# board.net
KiCad netlist of a schematic drawn in EAGLE
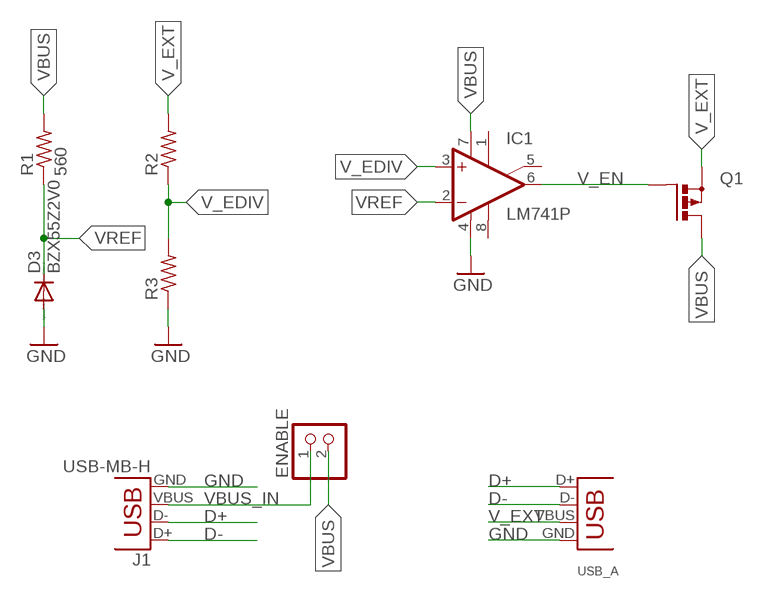
[diagram p0: schematic, sheet 1]

(export (version "E")
  (design (tool "Eeschema 10.0.6"))
  (components
    (comp (ref "D3")
      (value "BZX55Z2V0")
      (footprint "eagle-import:DO35-7")
      (libsource (lib "eagle-import") (part "1N4148DO35-7"))
    )
    (comp (ref "ENABLE")
      (value "PINHD-1X2")
      (footprint "eagle-import:1X02")
      (libsource (lib "eagle-import") (part "PINHD-1X2"))
    )
    (comp (ref "IC1")
      (value "LM741P")
      (footprint "eagle-import:DIL08")
      (libsource (lib "eagle-import") (part "741PLM"))
    )
    (comp (ref "J1")
      (value "USB-MB-H")
      (footprint "eagle-import:USB-MB-H")
      (libsource (lib "eagle-import") (part "USB-MB-H"))
    )
    (comp (ref "Q1")
      (value "PMOSFET_PTO220BV")
      (footprint "eagle-import:TO220BV")
      (libsource (lib "eagle-import") (part "PMOSFET_PTO220BV"))
    )
    (comp (ref "R1")
      (value "560")
      (footprint "eagle-import:0207_7")
      (libsource (lib "eagle-import") (part "R-US_0207/7"))
    )
    (comp (ref "R2")
      (value "R-US_0207/7")
      (footprint "eagle-import:0207_7")
      (libsource (lib "eagle-import") (part "R-US_0207/7"))
    )
    (comp (ref "R3")
      (value "R-US_0207/7")
      (footprint "eagle-import:0207_7")
      (libsource (lib "eagle-import") (part "R-US_0207/7"))
    )
    (comp (ref "USB_A")
      (value "USB-A-H")
      (footprint "eagle-import:USB-A-H")
      (libsource (lib "eagle-import") (part "USB-A-H"))
    )
  )
  (nets
    (net (code "1") (name "/D+") (class "Default")
      (node (ref "J1") (pin "D-") (pinfunction "D-_D-") (pintype "bidirectional"))
      (node (ref "USB_A") (pin "D+") (pinfunction "D+_D+") (pintype "bidirectional"))
    )
    (net (code "2") (name "/D-") (class "Default")
      (node (ref "J1") (pin "D+") (pinfunction "D+_D+") (pintype "bidirectional"))
      (node (ref "USB_A") (pin "D-") (pinfunction "D-_D-") (pintype "bidirectional"))
    )
    (net (code "3") (name "/VBUS_IN") (class "Default")
      (node (ref "ENABLE") (pin "1") (pinfunction "1_1") (pintype "passive"))
      (node (ref "J1") (pin "VBUS") (pinfunction "VBUS_VBUS") (pintype "bidirectional"))
    )
    (net (code "4") (name "/V_EN") (class "Default")
      (node (ref "IC1") (pin "6") (pinfunction "OUT_6") (pintype "output"))
      (node (ref "Q1") (pin "G") (pinfunction "G_G") (pintype "passive"))
    )
    (net (code "5") (name "GND") (class "Default")
      (node (ref "D3") (pin "A") (pinfunction "A_A") (pintype "passive"))
      (node (ref "IC1") (pin "4") (pinfunction "V-_4") (pintype "power_in"))
      (node (ref "J1") (pin "GND") (pinfunction "GND_GND") (pintype "bidirectional"))
      (node (ref "R3") (pin "1") (pinfunction "1_1") (pintype "passive"))
      (node (ref "USB_A") (pin "GND") (pinfunction "GND_GND") (pintype "bidirectional"))
    )
    (net (code "6") (name "VBUS") (class "Default")
      (node (ref "ENABLE") (pin "2") (pinfunction "2_2") (pintype "passive"))
      (node (ref "IC1") (pin "7") (pinfunction "V+_7") (pintype "power_in"))
      (node (ref "Q1") (pin "D") (pinfunction "D_D") (pintype "passive"))
      (node (ref "R1") (pin "2") (pinfunction "2_2") (pintype "passive"))
    )
    (net (code "7") (name "VREF") (class "Default")
      (node (ref "D3") (pin "C") (pinfunction "C_C") (pintype "passive"))
      (node (ref "IC1") (pin "2") (pinfunction "-IN_2") (pintype "input"))
      (node (ref "R1") (pin "1") (pinfunction "1_1") (pintype "passive"))
    )
    (net (code "8") (name "V_EDIV") (class "Default")
      (node (ref "IC1") (pin "3") (pinfunction "+IN_3") (pintype "input"))
      (node (ref "R2") (pin "1") (pinfunction "1_1") (pintype "passive"))
      (node (ref "R3") (pin "2") (pinfunction "2_2") (pintype "passive"))
    )
    (net (code "9") (name "V_EXT") (class "Default")
      (node (ref "Q1") (pin "S") (pinfunction "S_S") (pintype "passive"))
      (node (ref "R2") (pin "2") (pinfunction "2_2") (pintype "passive"))
      (node (ref "USB_A") (pin "VBUS") (pinfunction "VBUS_VBUS") (pintype "bidirectional"))
    )
    (net (code "10") (name "unconnected-(IC1-ON1-Pad1)") (class "Default")
      (node (ref "IC1") (pin "1") (pinfunction "ON1_1") (pintype "passive"))
    )
    (net (code "11") (name "unconnected-(IC1-ON2-Pad5)") (class "Default")
      (node (ref "IC1") (pin "5") (pinfunction "ON2_5") (pintype "passive"))
    )
    (net (code "12") (name "unconnected-(IC1-OPT-Pad8)") (class "Default")
      (node (ref "IC1") (pin "8") (pinfunction "OPT_8") (pintype "passive"))
    )
  )
)
